# warship_demo_2.net
KiCad netlist of a schematic drawn in Altium Designer
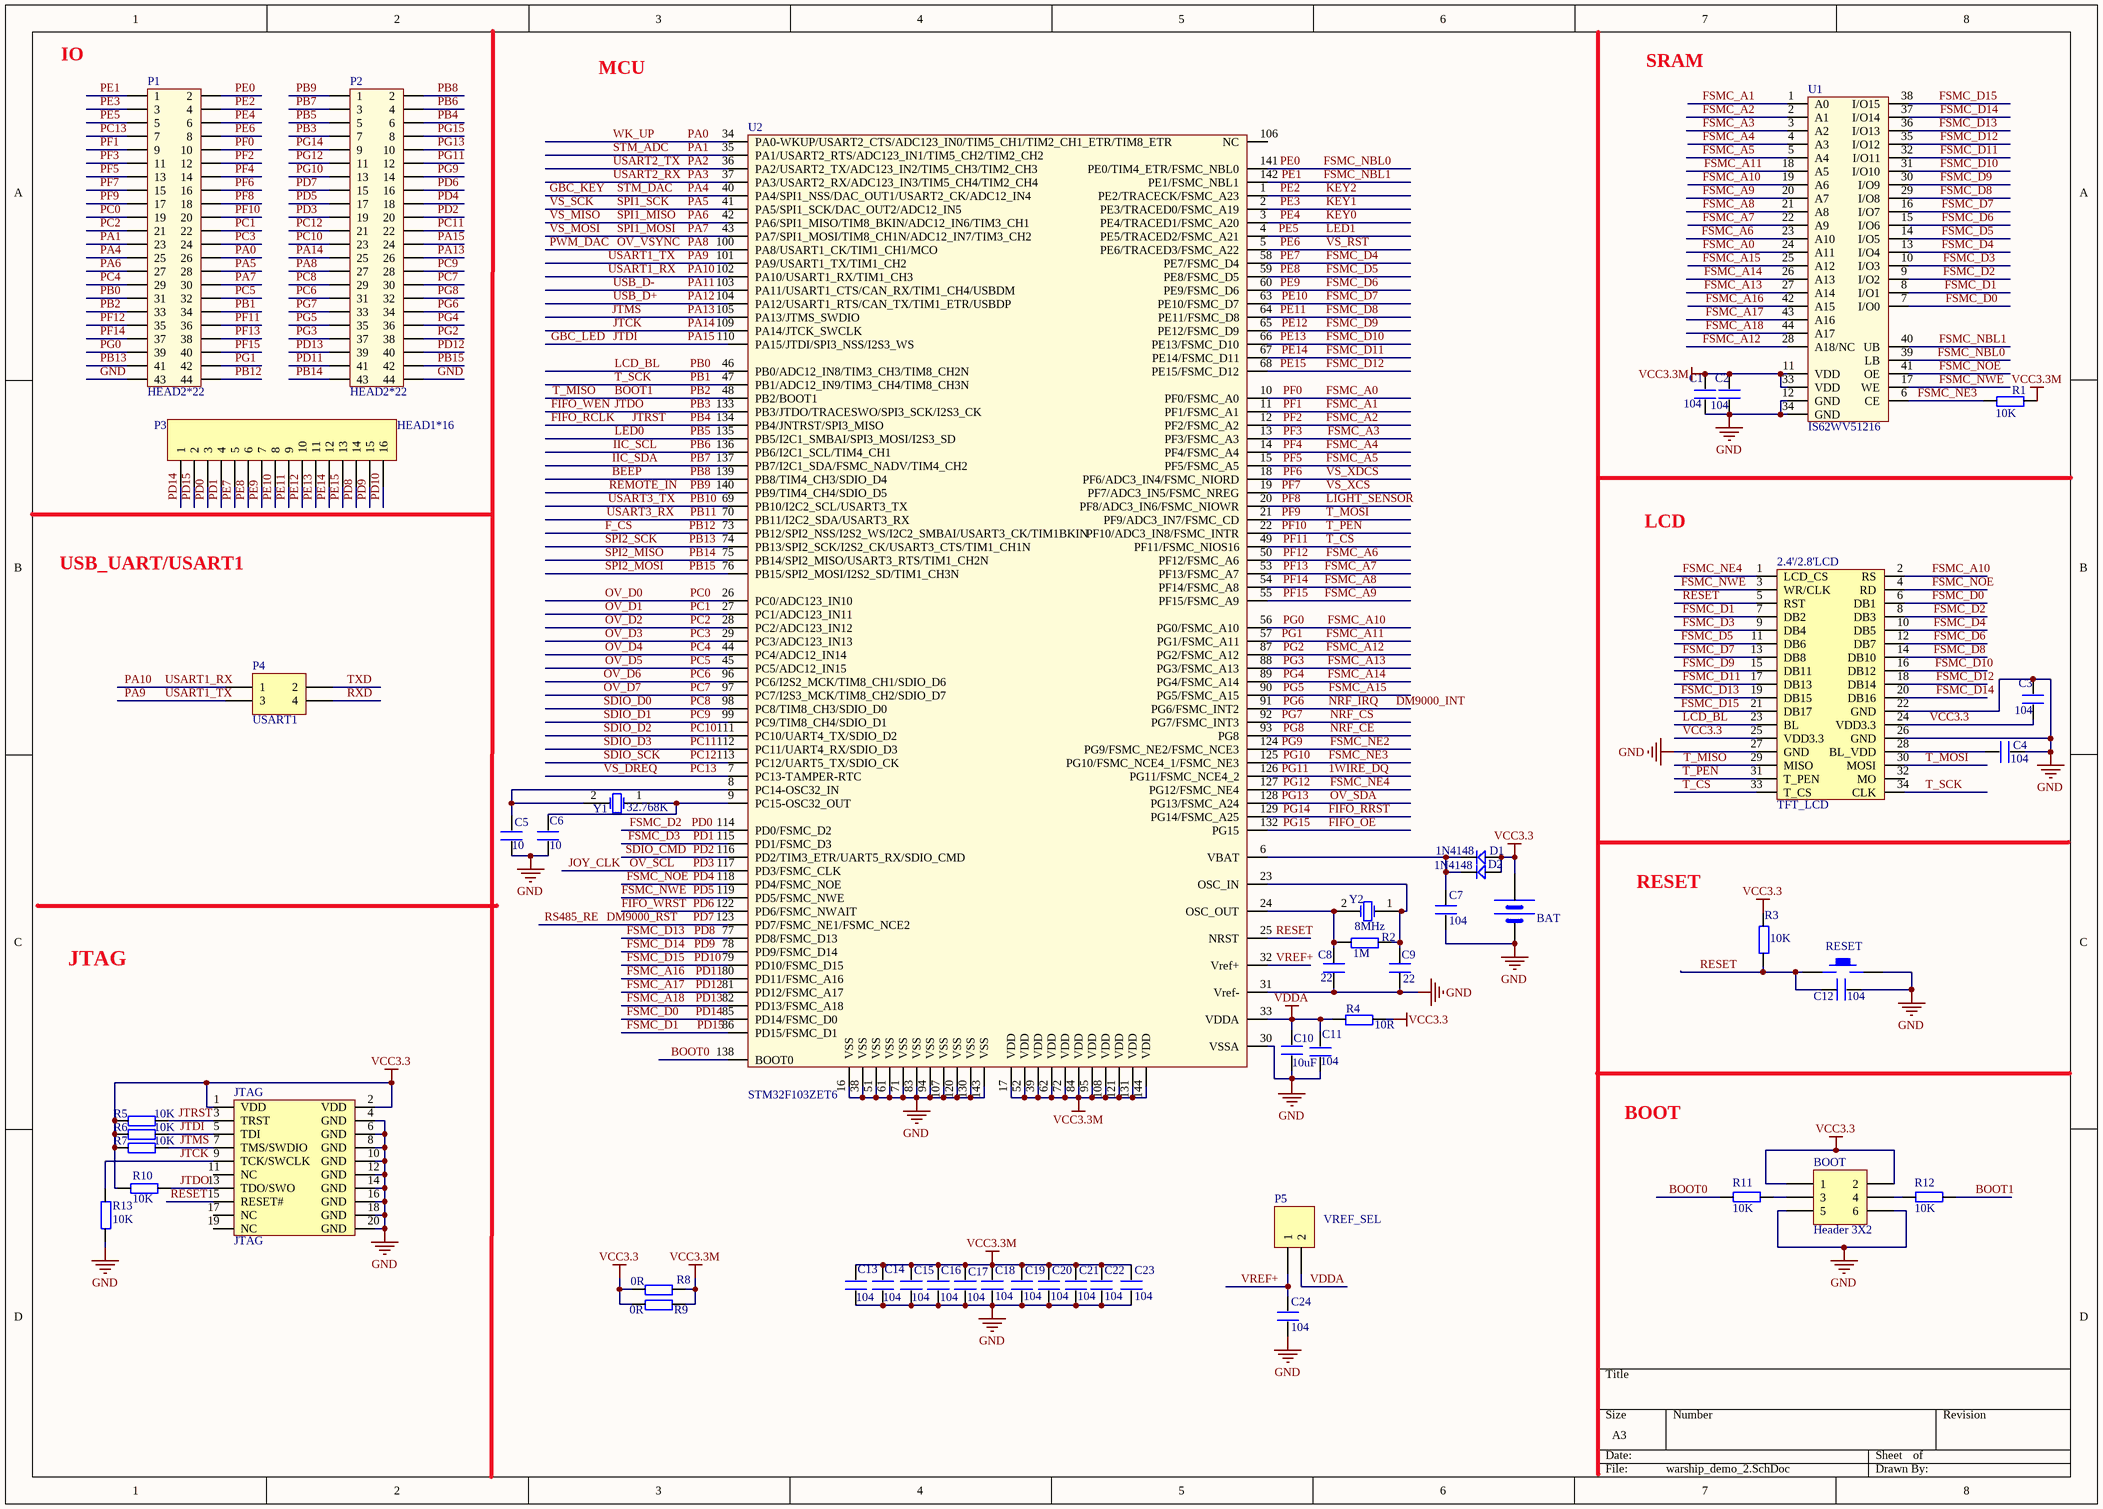
[diagram p0: warship_demo_2.SchDoc]

(export (version "E")
  (design (tool "Eeschema 10.0.6"))
  (components
    (comp (ref "2.4'/2.8'LCD")
      (value "TFT_LCD")
      (footprint "db2*17-4.3")
      (libsource (lib "WarShip V3 STM32103封装库") (part "TFT_LCD"))
    )
    (comp (ref "BAT")
      (value "BATT")
      (footprint "BATM")
      (libsource (lib "WarShip V3 STM32103封装库") (part "BAT"))
    )
    (comp (ref "BOOT")
      (value "Header 3X2")
      (footprint "HDR2X3")
      (description "Header, 3-Pin, Dual row")
      (fields (field (name "PUBLISHER") "Altium Limited"))
      (libsource (lib "WarShip V3 STM32103封装库") (part "Header 3X2"))
    )
    (comp (ref "C1") (value "104") (footprint "0603P") (libsource (lib "WarShip V3 STM32103封装库") (part "C")))
    (comp (ref "C2") (value "104") (footprint "0603P") (libsource (lib "WarShip V3 STM32103封装库") (part "C")))
    (comp (ref "C3") (value "104") (footprint "0603P") (libsource (lib "WarShip V3 STM32103封装库") (part "C")))
    (comp (ref "C4") (value "104") (footprint "0603P") (libsource (lib "WarShip V3 STM32103封装库") (part "C")))
    (comp (ref "C5") (value "10") (footprint "0603P") (libsource (lib "WarShip V3 STM32103封装库") (part "C")))
    (comp (ref "C6") (value "10") (footprint "0603P") (libsource (lib "WarShip V3 STM32103封装库") (part "C")))
    (comp (ref "C7") (value "104") (footprint "0603P") (libsource (lib "WarShip V3 STM32103封装库") (part "C")))
    (comp (ref "C8") (value "22") (footprint "0603P") (libsource (lib "WarShip V3 STM32103封装库") (part "C")))
    (comp (ref "C9") (value "22") (footprint "0603P") (libsource (lib "WarShip V3 STM32103封装库") (part "C")))
    (comp (ref "C10") (value "10uF") (footprint "0805") (libsource (lib "WarShip V3 STM32103封装库") (part "C")))
    (comp (ref "C11") (value "104") (footprint "0603P") (libsource (lib "WarShip V3 STM32103封装库") (part "C")))
    (comp (ref "C12") (value "104") (footprint "0603P") (libsource (lib "WarShip V3 STM32103封装库") (part "C")))
    (comp (ref "C13") (value "104") (footprint "0603P") (libsource (lib "WarShip V3 STM32103封装库") (part "C")))
    (comp (ref "C14") (value "104") (footprint "0603P") (libsource (lib "WarShip V3 STM32103封装库") (part "C")))
    (comp (ref "C15") (value "104") (footprint "0603P") (libsource (lib "WarShip V3 STM32103封装库") (part "C")))
    (comp (ref "C16") (value "104") (footprint "0603P") (libsource (lib "WarShip V3 STM32103封装库") (part "C")))
    (comp (ref "C17") (value "104") (footprint "0603P") (libsource (lib "WarShip V3 STM32103封装库") (part "C")))
    (comp (ref "C18") (value "104") (footprint "0603P") (libsource (lib "WarShip V3 STM32103封装库") (part "C")))
    (comp (ref "C19") (value "104") (footprint "0603P") (libsource (lib "WarShip V3 STM32103封装库") (part "C")))
    (comp (ref "C20") (value "104") (footprint "0603P") (libsource (lib "WarShip V3 STM32103封装库") (part "C")))
    (comp (ref "C21") (value "104") (footprint "0603P") (libsource (lib "WarShip V3 STM32103封装库") (part "C")))
    (comp (ref "C22") (value "104") (footprint "0603P") (libsource (lib "WarShip V3 STM32103封装库") (part "C")))
    (comp (ref "C23") (value "104") (footprint "0603P") (libsource (lib "WarShip V3 STM32103封装库") (part "C")))
    (comp (ref "C24") (value "104") (footprint "0603P") (libsource (lib "WarShip V3 STM32103封装库") (part "C")))
    (comp (ref "D1")
      (value "1N4148")
      (footprint "DIODE_SOP")
      (libsource (lib "WarShip V3 STM32103封装库") (part "D"))
    )
    (comp (ref "D2")
      (value "1N4148")
      (footprint "DIODE_SOP")
      (libsource (lib "WarShip V3 STM32103封装库") (part "D"))
    )
    (comp (ref "JTAG")
      (value "JTAG")
      (footprint "JTAG_20")
      (libsource (lib "WarShip V3 STM32103封装库") (part "JTAG"))
    )
    (comp (ref "P1")
      (value "HEAD2*22")
      (footprint "HEAD2*22")
      (libsource (lib "WarShip V3 STM32103封装库") (part "HEAD2*22"))
    )
    (comp (ref "P2")
      (value "HEAD2*22")
      (footprint "HEAD2*22")
      (libsource (lib "WarShip V3 STM32103封装库") (part "HEAD2*22"))
    )
    (comp (ref "P3")
      (value "HEAD1*16")
      (footprint "HDR1X16")
      (description "Header, 16-Pin")
      (fields (field (name "PUBLISHER") "Altium Limited"))
      (libsource (lib "WarShip V3 STM32103封装库") (part "Header 16"))
    )
    (comp (ref "P4")
      (value "USART1")
      (footprint "HDR2X2")
      (description "Header, 2-Pin, Dual row")
      (fields (field (name "PUBLISHER") "Altium Limited"))
      (libsource (lib "WarShip V3 STM32103封装库") (part "Header 2X2"))
    )
    (comp (ref "P5")
      (value "VREF_SEL")
      (footprint "HDR1X2")
      (description "Header, 2-Pin")
      (fields (field (name "PUBLISHER") "Altium Limited"))
      (libsource (lib "WarShip V3 STM32103封装库") (part "Header 2"))
    )
    (comp (ref "R1") (value "10K") (footprint "0603P") (libsource (lib "WarShip V3 STM32103封装库") (part "R")))
    (comp (ref "R2") (value "1M") (footprint "0603P") (libsource (lib "WarShip V3 STM32103封装库") (part "R")))
    (comp (ref "R3") (value "10K") (footprint "0603P") (libsource (lib "WarShip V3 STM32103封装库") (part "R")))
    (comp (ref "R4") (value "10R") (footprint "0603P") (libsource (lib "WarShip V3 STM32103封装库") (part "R")))
    (comp (ref "R5") (value "10K") (footprint "0603P") (libsource (lib "WarShip V3 STM32103封装库") (part "R")))
    (comp (ref "R6") (value "10K") (footprint "0603P") (libsource (lib "WarShip V3 STM32103封装库") (part "R")))
    (comp (ref "R7") (value "10K") (footprint "0603P") (libsource (lib "WarShip V3 STM32103封装库") (part "R")))
    (comp (ref "R8") (value "0R") (footprint "0603P") (libsource (lib "WarShip V3 STM32103封装库") (part "R")))
    (comp (ref "R9") (value "0R") (footprint "0603P") (libsource (lib "WarShip V3 STM32103封装库") (part "R")))
    (comp (ref "R10") (value "10K") (footprint "0603P") (libsource (lib "WarShip V3 STM32103封装库") (part "R")))
    (comp (ref "R11") (value "10K") (footprint "0603P") (libsource (lib "WarShip V3 STM32103封装库") (part "R")))
    (comp (ref "R12") (value "10K") (footprint "0603P") (libsource (lib "WarShip V3 STM32103封装库") (part "R")))
    (comp (ref "R13") (value "10K") (footprint "0603P") (libsource (lib "WarShip V3 STM32103封装库") (part "R")))
    (comp (ref "RESET")
      (value "KEY_M")
      (footprint "KEY_M")
      (libsource (lib "WarShip V3 STM32103封装库") (part "KEY_M"))
    )
    (comp (ref "U1")
      (value "IS62WV51216")
      (footprint "TSOP44")
      (libsource (lib "WarShip V3 STM32103封装库") (part "IS61LV51216"))
    )
    (comp (ref "U2")
      (value "STM32F103ZET6")
      (footprint "LQFP144")
      (libsource (lib "WarShip V3 STM32103封装库") (part "STM32F103ZET6"))
    )
    (comp (ref "Y1")
      (value "32.768K")
      (footprint "XTAL_US")
      (description "Crystal Oscillator")
      (fields (field (name "PUBLISHER") "Altium Limited"))
      (libsource (lib "WarShip V3 STM32103封装库") (part "XTAL"))
    )
    (comp (ref "Y2")
      (value "8MHz")
      (footprint "XTAL_US")
      (description "Crystal Oscillator")
      (fields (field (name "PUBLISHER") "Altium Limited"))
      (libsource (lib "WarShip V3 STM32103封装库") (part "XTAL"))
    )
  )
  (nets
    (net (code "1") (name "/1WIRE_DQ") (class "Default")
      (node (ref "P2") (pin "12") (pinfunction "12_12") (pintype "passive"))
      (node (ref "U2") (pin "126") (pinfunction "PG11/FSMC_NCE4_2_126") (pintype "passive"))
    )
    (net (code "2") (name "/BEEP") (class "Default")
      (node (ref "P2") (pin "2") (pinfunction "2_2") (pintype "passive"))
      (node (ref "U2") (pin "139") (pinfunction "PB8/TIM4_CH3/SDIO_D4_139") (pintype "passive"))
    )
    (net (code "3") (name "/BOOT0") (class "Default")
      (node (ref "R11") (pin "2") (pintype "passive"))
      (node (ref "U2") (pin "138") (pinfunction "BOOT0_138") (pintype "passive"))
    )
    (net (code "4") (name "/BOOT1") (class "Default")
      (node (ref "2.4'/2.8'LCD") (pin "29") (pinfunction "MISO_29") (pintype "passive"))
      (node (ref "P1") (pin "33") (pinfunction "33_33") (pintype "passive"))
      (node (ref "R12") (pin "1") (pintype "passive"))
      (node (ref "U2") (pin "48") (pinfunction "PB2/BOOT1_48") (pintype "passive"))
    )
    (net (code "5") (name "/DM9000_INT") (class "Default")
      (node (ref "P2") (pin "34") (pinfunction "34_34") (pintype "passive"))
      (node (ref "U2") (pin "91") (pinfunction "PG6/FSMC_INT2_91") (pintype "passive"))
    )
    (net (code "6") (name "/DM9000_RST") (class "Default")
      (node (ref "P2") (pin "15") (pinfunction "15_15") (pintype "passive"))
      (node (ref "U2") (pin "123") (pinfunction "PD7/FSMC_NE1/FSMC_NCE2_123") (pintype "passive"))
    )
    (net (code "7") (name "/FIFO_OE") (class "Default")
      (node (ref "P2") (pin "8") (pinfunction "8_8") (pintype "passive"))
      (node (ref "U2") (pin "132") (pinfunction "PG15_132") (pintype "passive"))
    )
    (net (code "8") (name "/FIFO_RCLK") (class "Default")
      (node (ref "JTAG") (pin "3") (pinfunction "TRST_3") (pintype "passive"))
      (node (ref "P2") (pin "6") (pinfunction "6_6") (pintype "passive"))
      (node (ref "R5") (pin "2") (pintype "passive"))
      (node (ref "U2") (pin "134") (pinfunction "PB4/JNTRST/SPI3_MISO_134") (pintype "passive"))
    )
    (net (code "9") (name "/FIFO_RRST") (class "Default")
      (node (ref "P2") (pin "9") (pinfunction "9_9") (pintype "passive"))
      (node (ref "U2") (pin "129") (pinfunction "PG14/FSMC_A25_129") (pintype "passive"))
    )
    (net (code "10") (name "/FIFO_WEN") (class "Default")
      (node (ref "JTAG") (pin "13") (pinfunction "TDO/SWO_13") (pintype "passive"))
      (node (ref "P2") (pin "7") (pinfunction "7_7") (pintype "passive"))
      (node (ref "R10") (pin "2") (pintype "passive"))
      (node (ref "U2") (pin "133") (pinfunction "PB3/JTDO/TRACESWO/SPI3_SCK/I2S3_CK_133") (pintype "passive"))
    )
    (net (code "11") (name "/FIFO_WRST") (class "Default")
      (node (ref "P2") (pin "16") (pinfunction "16_16") (pintype "passive"))
      (node (ref "U2") (pin "122") (pinfunction "PD6/FSMC_NWAIT_122") (pintype "passive"))
    )
    (net (code "12") (name "/FSMC_A0") (class "Default")
      (node (ref "P1") (pin "10") (pinfunction "10_10") (pintype "passive"))
      (node (ref "U1") (pin "24") (pinfunction "A11_24") (pintype "passive"))
      (node (ref "U2") (pin "10") (pinfunction "PF0/FSMC_A0_10") (pintype "passive"))
    )
    (net (code "13") (name "/FSMC_A1") (class "Default")
      (node (ref "P1") (pin "9") (pinfunction "9_9") (pintype "passive"))
      (node (ref "U1") (pin "1") (pinfunction "A0_1") (pintype "passive"))
      (node (ref "U2") (pin "11") (pinfunction "PF1/FSMC_A1_11") (pintype "passive"))
    )
    (net (code "14") (name "/FSMC_A2") (class "Default")
      (node (ref "P1") (pin "12") (pinfunction "12_12") (pintype "passive"))
      (node (ref "U1") (pin "2") (pinfunction "A1_2") (pintype "passive"))
      (node (ref "U2") (pin "12") (pinfunction "PF2/FSMC_A2_12") (pintype "passive"))
    )
    (net (code "15") (name "/FSMC_A3") (class "Default")
      (node (ref "P1") (pin "11") (pinfunction "11_11") (pintype "passive"))
      (node (ref "U1") (pin "3") (pinfunction "A2_3") (pintype "passive"))
      (node (ref "U2") (pin "13") (pinfunction "PF3/FSMC_A3_13") (pintype "passive"))
    )
    (net (code "16") (name "/FSMC_A4") (class "Default")
      (node (ref "P1") (pin "14") (pinfunction "14_14") (pintype "passive"))
      (node (ref "U1") (pin "4") (pinfunction "A3_4") (pintype "passive"))
      (node (ref "U2") (pin "14") (pinfunction "PF4/FSMC_A4_14") (pintype "passive"))
    )
    (net (code "17") (name "/FSMC_A5") (class "Default")
      (node (ref "P1") (pin "13") (pinfunction "13_13") (pintype "passive"))
      (node (ref "U1") (pin "5") (pinfunction "A4_5") (pintype "passive"))
      (node (ref "U2") (pin "15") (pinfunction "PF5/FSMC_A5_15") (pintype "passive"))
    )
    (net (code "18") (name "/FSMC_A6") (class "Default")
      (node (ref "P1") (pin "35") (pinfunction "35_35") (pintype "passive"))
      (node (ref "U1") (pin "23") (pinfunction "A10_23") (pintype "passive"))
      (node (ref "U2") (pin "50") (pinfunction "PF12/FSMC_A6_50") (pintype "passive"))
    )
    (net (code "19") (name "/FSMC_A7") (class "Default")
      (node (ref "P1") (pin "38") (pinfunction "38_38") (pintype "passive"))
      (node (ref "U1") (pin "22") (pinfunction "A9_22") (pintype "passive"))
      (node (ref "U2") (pin "53") (pinfunction "PF13/FSMC_A7_53") (pintype "passive"))
    )
    (net (code "20") (name "/FSMC_A8") (class "Default")
      (node (ref "P1") (pin "37") (pinfunction "37_37") (pintype "passive"))
      (node (ref "U1") (pin "21") (pinfunction "A8_21") (pintype "passive"))
      (node (ref "U2") (pin "54") (pinfunction "PF14/FSMC_A8_54") (pintype "passive"))
    )
    (net (code "21") (name "/FSMC_A9") (class "Default")
      (node (ref "P1") (pin "40") (pinfunction "40_40") (pintype "passive"))
      (node (ref "U1") (pin "20") (pinfunction "A7_20") (pintype "passive"))
      (node (ref "U2") (pin "55") (pinfunction "PF15/FSMC_A9_55") (pintype "passive"))
    )
    (net (code "22") (name "/FSMC_A10") (class "Default")
      (node (ref "2.4'/2.8'LCD") (pin "2") (pinfunction "RS_2") (pintype "passive"))
      (node (ref "P1") (pin "39") (pinfunction "39_39") (pintype "passive"))
      (node (ref "U1") (pin "19") (pinfunction "A6_19") (pintype "passive"))
      (node (ref "U2") (pin "56") (pinfunction "PG0/FSMC_A10_56") (pintype "passive"))
    )
    (net (code "23") (name "/FSMC_A11") (class "Default")
      (node (ref "P1") (pin "42") (pinfunction "42_42") (pintype "passive"))
      (node (ref "U1") (pin "18") (pinfunction "A5_18") (pintype "passive"))
      (node (ref "U2") (pin "57") (pinfunction "PG1/FSMC_A11_57") (pintype "passive"))
    )
    (net (code "24") (name "/FSMC_A12") (class "Default")
      (node (ref "P2") (pin "38") (pinfunction "38_38") (pintype "passive"))
      (node (ref "U1") (pin "28") (pinfunction "A18/NC_28") (pintype "passive"))
      (node (ref "U2") (pin "87") (pinfunction "PG2/FSMC_A12_87") (pintype "passive"))
    )
    (net (code "25") (name "/FSMC_A13") (class "Default")
      (node (ref "P2") (pin "37") (pinfunction "37_37") (pintype "passive"))
      (node (ref "U1") (pin "27") (pinfunction "A14_27") (pintype "passive"))
      (node (ref "U2") (pin "88") (pinfunction "PG3/FSMC_A13_88") (pintype "passive"))
    )
    (net (code "26") (name "/FSMC_A14") (class "Default")
      (node (ref "P2") (pin "36") (pinfunction "36_36") (pintype "passive"))
      (node (ref "U1") (pin "26") (pinfunction "A13_26") (pintype "passive"))
      (node (ref "U2") (pin "89") (pinfunction "PG4/FSMC_A14_89") (pintype "passive"))
    )
    (net (code "27") (name "/FSMC_A15") (class "Default")
      (node (ref "P2") (pin "35") (pinfunction "35_35") (pintype "passive"))
      (node (ref "U1") (pin "25") (pinfunction "A12_25") (pintype "passive"))
      (node (ref "U2") (pin "90") (pinfunction "PG5/FSMC_A15_90") (pintype "passive"))
    )
    (net (code "28") (name "/FSMC_A16") (class "Default")
      (node (ref "P2") (pin "41") (pinfunction "41_41") (pintype "passive"))
      (node (ref "U1") (pin "42") (pinfunction "A15_42") (pintype "passive"))
      (node (ref "U2") (pin "80") (pinfunction "PD11/FSMC_A16_80") (pintype "passive"))
    )
    (net (code "29") (name "/FSMC_A17") (class "Default")
      (node (ref "P2") (pin "40") (pinfunction "40_40") (pintype "passive"))
      (node (ref "U1") (pin "43") (pinfunction "A16_43") (pintype "passive"))
      (node (ref "U2") (pin "81") (pinfunction "PD12/FSMC_A17_81") (pintype "passive"))
    )
    (net (code "30") (name "/FSMC_A18") (class "Default")
      (node (ref "P2") (pin "39") (pinfunction "39_39") (pintype "passive"))
      (node (ref "U1") (pin "44") (pinfunction "A17_44") (pintype "passive"))
      (node (ref "U2") (pin "82") (pinfunction "PD13/FSMC_A18_82") (pintype "passive"))
    )
    (net (code "31") (name "/FSMC_D0") (class "Default")
      (node (ref "2.4'/2.8'LCD") (pin "6") (pinfunction "DB1_6") (pintype "passive"))
      (node (ref "P3") (pin "1") (pinfunction "1_1") (pintype "passive"))
      (node (ref "U1") (pin "7") (pinfunction "I/O0_7") (pintype "passive"))
      (node (ref "U2") (pin "85") (pinfunction "PD14/FSMC_D0_85") (pintype "passive"))
    )
    (net (code "32") (name "/FSMC_D1") (class "Default")
      (node (ref "2.4'/2.8'LCD") (pin "7") (pinfunction "DB2_7") (pintype "passive"))
      (node (ref "P3") (pin "2") (pinfunction "2_2") (pintype "passive"))
      (node (ref "U1") (pin "8") (pinfunction "I/O1_8") (pintype "passive"))
      (node (ref "U2") (pin "86") (pinfunction "PD15/FSMC_D1_86") (pintype "passive"))
    )
    (net (code "33") (name "/FSMC_D2") (class "Default")
      (node (ref "2.4'/2.8'LCD") (pin "8") (pinfunction "DB3_8") (pintype "passive"))
      (node (ref "P3") (pin "3") (pinfunction "3_3") (pintype "passive"))
      (node (ref "U1") (pin "9") (pinfunction "I/O2_9") (pintype "passive"))
      (node (ref "U2") (pin "114") (pinfunction "PD0/FSMC_D2_114") (pintype "passive"))
    )
    (net (code "34") (name "/FSMC_D3") (class "Default")
      (node (ref "2.4'/2.8'LCD") (pin "9") (pinfunction "DB4_9") (pintype "passive"))
      (node (ref "P3") (pin "4") (pinfunction "4_4") (pintype "passive"))
      (node (ref "U1") (pin "10") (pinfunction "I/O3_10") (pintype "passive"))
      (node (ref "U2") (pin "115") (pinfunction "PD1/FSMC_D3_115") (pintype "passive"))
    )
    (net (code "35") (name "/FSMC_D4") (class "Default")
      (node (ref "2.4'/2.8'LCD") (pin "10") (pinfunction "DB5_10") (pintype "passive"))
      (node (ref "P3") (pin "5") (pinfunction "5_5") (pintype "passive"))
      (node (ref "U1") (pin "13") (pinfunction "I/O4_13") (pintype "passive"))
      (node (ref "U2") (pin "58") (pinfunction "PE7/FSMC_D4_58") (pintype "passive"))
    )
    (net (code "36") (name "/FSMC_D5") (class "Default")
      (node (ref "2.4'/2.8'LCD") (pin "11") (pinfunction "DB6_11") (pintype "passive"))
      (node (ref "P3") (pin "6") (pinfunction "6_6") (pintype "passive"))
      (node (ref "U1") (pin "14") (pinfunction "I/O5_14") (pintype "passive"))
      (node (ref "U2") (pin "59") (pinfunction "PE8/FSMC_D5_59") (pintype "passive"))
    )
    (net (code "37") (name "/FSMC_D6") (class "Default")
      (node (ref "2.4'/2.8'LCD") (pin "12") (pinfunction "DB7_12") (pintype "passive"))
      (node (ref "P3") (pin "7") (pinfunction "7_7") (pintype "passive"))
      (node (ref "U1") (pin "15") (pinfunction "I/O6_15") (pintype "passive"))
      (node (ref "U2") (pin "60") (pinfunction "PE9/FSMC_D6_60") (pintype "passive"))
    )
    (net (code "38") (name "/FSMC_D7") (class "Default")
      (node (ref "2.4'/2.8'LCD") (pin "13") (pinfunction "DB8_13") (pintype "passive"))
      (node (ref "P3") (pin "8") (pinfunction "8_8") (pintype "passive"))
      (node (ref "U1") (pin "16") (pinfunction "I/O7_16") (pintype "passive"))
      (node (ref "U2") (pin "63") (pinfunction "PE10/FSMC_D7_63") (pintype "passive"))
    )
    (net (code "39") (name "/FSMC_D8") (class "Default")
      (node (ref "2.4'/2.8'LCD") (pin "14") (pinfunction "DB10_14") (pintype "passive"))
      (node (ref "P3") (pin "9") (pinfunction "9_9") (pintype "passive"))
      (node (ref "U1") (pin "29") (pinfunction "I/O8_29") (pintype "passive"))
      (node (ref "U2") (pin "64") (pinfunction "PE11/FSMC_D8_64") (pintype "passive"))
    )
    (net (code "40") (name "/FSMC_D9") (class "Default")
      (node (ref "2.4'/2.8'LCD") (pin "15") (pinfunction "DB11_15") (pintype "passive"))
      (node (ref "P3") (pin "10") (pinfunction "10_10") (pintype "passive"))
      (node (ref "U1") (pin "30") (pinfunction "I/O9_30") (pintype "passive"))
      (node (ref "U2") (pin "65") (pinfunction "PE12/FSMC_D9_65") (pintype "passive"))
    )
    (net (code "41") (name "/FSMC_D10") (class "Default")
      (node (ref "2.4'/2.8'LCD") (pin "16") (pinfunction "DB12_16") (pintype "passive"))
      (node (ref "P3") (pin "11") (pinfunction "11_11") (pintype "passive"))
      (node (ref "U1") (pin "31") (pinfunction "I/O10_31") (pintype "passive"))
      (node (ref "U2") (pin "66") (pinfunction "PE13/FSMC_D10_66") (pintype "passive"))
    )
    (net (code "42") (name "/FSMC_D11") (class "Default")
      (node (ref "2.4'/2.8'LCD") (pin "17") (pinfunction "DB13_17") (pintype "passive"))
      (node (ref "P3") (pin "12") (pinfunction "12_12") (pintype "passive"))
      (node (ref "U1") (pin "32") (pinfunction "I/O11_32") (pintype "passive"))
      (node (ref "U2") (pin "67") (pinfunction "PE14/FSMC_D11_67") (pintype "passive"))
    )
    (net (code "43") (name "/FSMC_D12") (class "Default")
      (node (ref "2.4'/2.8'LCD") (pin "18") (pinfunction "DB14_18") (pintype "passive"))
      (node (ref "P3") (pin "13") (pinfunction "13_13") (pintype "passive"))
      (node (ref "U1") (pin "35") (pinfunction "I/O12_35") (pintype "passive"))
      (node (ref "U2") (pin "68") (pinfunction "PE15/FSMC_D12_68") (pintype "passive"))
    )
    (net (code "44") (name "/FSMC_D13") (class "Default")
      (node (ref "2.4'/2.8'LCD") (pin "19") (pinfunction "DB15_19") (pintype "passive"))
      (node (ref "P3") (pin "14") (pinfunction "14_14") (pintype "passive"))
      (node (ref "U1") (pin "36") (pinfunction "I/O13_36") (pintype "passive"))
      (node (ref "U2") (pin "77") (pinfunction "PD8/FSMC_D13_77") (pintype "passive"))
    )
    (net (code "45") (name "/FSMC_D14") (class "Default")
      (node (ref "2.4'/2.8'LCD") (pin "20") (pinfunction "DB16_20") (pintype "passive"))
      (node (ref "P3") (pin "15") (pinfunction "15_15") (pintype "passive"))
      (node (ref "U1") (pin "37") (pinfunction "I/O14_37") (pintype "passive"))
      (node (ref "U2") (pin "78") (pinfunction "PD9/FSMC_D14_78") (pintype "passive"))
    )
    (net (code "46") (name "/FSMC_D15") (class "Default")
      (node (ref "2.4'/2.8'LCD") (pin "21") (pinfunction "DB17_21") (pintype "passive"))
      (node (ref "P3") (pin "16") (pinfunction "16_16") (pintype "passive"))
      (node (ref "U1") (pin "38") (pinfunction "I/O15_38") (pintype "passive"))
      (node (ref "U2") (pin "79") (pinfunction "PD10/FSMC_D15_79") (pintype "passive"))
    )
    (net (code "47") (name "/FSMC_NBL0") (class "Default")
      (node (ref "P1") (pin "2") (pinfunction "2_2") (pintype "passive"))
      (node (ref "U1") (pin "39") (pinfunction "LB_39") (pintype "passive"))
      (node (ref "U2") (pin "141") (pinfunction "PE0/TIM4_ETR/FSMC_NBL0_141") (pintype "passive"))
    )
    (net (code "48") (name "/FSMC_NBL1") (class "Default")
      (node (ref "P1") (pin "1") (pinfunction "1_1") (pintype "passive"))
      (node (ref "U1") (pin "40") (pinfunction "UB_40") (pintype "passive"))
      (node (ref "U2") (pin "142") (pinfunction "PE1/FSMC_NBL1_142") (pintype "passive"))
    )
    (net (code "49") (name "/FSMC_NE2") (class "Default")
      (node (ref "P2") (pin "14") (pinfunction "14_14") (pintype "passive"))
      (node (ref "U2") (pin "124") (pinfunction "PG9/FSMC_NE2/FSMC_NCE3_124") (pintype "passive"))
    )
    (net (code "50") (name "/FSMC_NE3") (class "Default")
      (node (ref "P2") (pin "13") (pinfunction "13_13") (pintype "passive"))
      (node (ref "R1") (pin "1") (pintype "passive"))
      (node (ref "U1") (pin "6") (pinfunction "CE_6") (pintype "passive"))
      (node (ref "U2") (pin "125") (pinfunction "PG10/FSMC_NCE4_1/FSMC_NE3_125") (pintype "passive"))
    )
    (net (code "51") (name "/FSMC_NE4") (class "Default")
      (node (ref "2.4'/2.8'LCD") (pin "1") (pinfunction "LCD_CS_1") (pintype "passive"))
      (node (ref "P2") (pin "11") (pinfunction "11_11") (pintype "passive"))
      (node (ref "U2") (pin "127") (pinfunction "PG12/FSMC_NE4_127") (pintype "passive"))
    )
    (net (code "52") (name "/FSMC_NOE") (class "Default")
      (node (ref "2.4'/2.8'LCD") (pin "4") (pinfunction "RD_4") (pintype "passive"))
      (node (ref "P2") (pin "18") (pinfunction "18_18") (pintype "passive"))
      (node (ref "U1") (pin "41") (pinfunction "OE_41") (pintype "passive"))
      (node (ref "U2") (pin "118") (pinfunction "PD4/FSMC_NOE_118") (pintype "passive"))
    )
    (net (code "53") (name "/FSMC_NWE") (class "Default")
      (node (ref "2.4'/2.8'LCD") (pin "3") (pinfunction "WR/CLK_3") (pintype "passive"))
      (node (ref "P2") (pin "17") (pinfunction "17_17") (pintype "passive"))
      (node (ref "U1") (pin "17") (pinfunction "WE_17") (pintype "passive"))
      (node (ref "U2") (pin "119") (pinfunction "PD5/FSMC_NWE_119") (pintype "passive"))
    )
    (net (code "54") (name "/F_CS") (class "Default")
      (node (ref "P1") (pin "44") (pinfunction "44_44") (pintype "passive"))
      (node (ref "U2") (pin "73") (pinfunction "PB12/SPI2_NSS/I2S2_WS/I2C2_SMBAI/USART3_CK/TIM1BKIN_73") (pintype "passive"))
    )
    (net (code "55") (name "/GBC_KEY") (class "Default")
      (node (ref "P1") (pin "25") (pinfunction "25_25") (pintype "passive"))
      (node (ref "U2") (pin "40") (pinfunction "PA4/SPI1_NSS/DAC_OUT1/USART2_CK/ADC12_IN4_40") (pintype "passive"))
    )
    (net (code "56") (name "/GBC_LED") (class "Default")
      (node (ref "JTAG") (pin "5") (pinfunction "TDI_5") (pintype "passive"))
      (node (ref "P2") (pin "24") (pinfunction "24_24") (pintype "passive"))
      (node (ref "R6") (pin "2") (pintype "passive"))
      (node (ref "U2") (pin "110") (pinfunction "PA15/JTDI/SPI3_NSS/I2S3_WS_110") (pintype "passive"))
    )
    (net (code "57") (name "/IIC_SCL") (class "Default")
      (node (ref "P2") (pin "4") (pinfunction "4_4") (pintype "passive"))
      (node (ref "U2") (pin "136") (pinfunction "PB6/I2C1_SCL/TIM4_CH1_136") (pintype "passive"))
    )
    (net (code "58") (name "/IIC_SDA") (class "Default")
      (node (ref "P2") (pin "3") (pinfunction "3_3") (pintype "passive"))
      (node (ref "U2") (pin "137") (pinfunction "PB7/I2C1_SDA/FSMC_NADV/TIM4_CH2_137") (pintype "passive"))
    )
    (net (code "59") (name "/JOY_CLK") (class "Default")
      (node (ref "P2") (pin "19") (pinfunction "19_19") (pintype "passive"))
      (node (ref "U2") (pin "117") (pinfunction "PD3/FSMC_CLK_117") (pintype "passive"))
    )
    (net (code "60") (name "/JTCK") (class "Default")
      (node (ref "JTAG") (pin "9") (pinfunction "TCK/SWCLK_9") (pintype "passive"))
      (node (ref "P2") (pin "25") (pinfunction "25_25") (pintype "passive"))
      (node (ref "R13") (pin "2") (pintype "passive"))
      (node (ref "U2") (pin "109") (pinfunction "PA14/JTCK_SWCLK_109") (pintype "passive"))
    )
    (net (code "61") (name "/JTMS") (class "Default")
      (node (ref "JTAG") (pin "7") (pinfunction "TMS/SWDIO_7") (pintype "passive"))
      (node (ref "P2") (pin "26") (pinfunction "26_26") (pintype "passive"))
      (node (ref "R7") (pin "2") (pintype "passive"))
      (node (ref "U2") (pin "105") (pinfunction "PA13/JTMS_SWDIO_105") (pintype "passive"))
    )
    (net (code "62") (name "/KEY0") (class "Default")
      (node (ref "P1") (pin "6") (pinfunction "6_6") (pintype "passive"))
      (node (ref "U2") (pin "3") (pinfunction "PE4/TRACED1/FSMC_A20_3") (pintype "passive"))
    )
    (net (code "63") (name "/KEY1") (class "Default")
      (node (ref "P1") (pin "3") (pinfunction "3_3") (pintype "passive"))
      (node (ref "U2") (pin "2") (pinfunction "PE3/TRACED0/FSMC_A19_2") (pintype "passive"))
    )
    (net (code "64") (name "/KEY2") (class "Default")
      (node (ref "P1") (pin "4") (pinfunction "4_4") (pintype "passive"))
      (node (ref "U2") (pin "1") (pinfunction "PE2/TRACECK/FSMC_A23_1") (pintype "passive"))
    )
    (net (code "65") (name "/LCD_BL") (class "Default")
      (node (ref "2.4'/2.8'LCD") (pin "23") (pinfunction "BL_23") (pintype "passive"))
      (node (ref "P1") (pin "31") (pinfunction "31_31") (pintype "passive"))
      (node (ref "U2") (pin "46") (pinfunction "PB0/ADC12_IN8/TIM3_CH3/TIM8_CH2N_46") (pintype "passive"))
    )
    (net (code "66") (name "/LED0") (class "Default")
      (node (ref "P2") (pin "5") (pinfunction "5_5") (pintype "passive"))
      (node (ref "U2") (pin "135") (pinfunction "PB5/I2C1_SMBAI/SPI3_MOSI/I2S3_SD_135") (pintype "passive"))
    )
    (net (code "67") (name "/LED1") (class "Default")
      (node (ref "P1") (pin "5") (pinfunction "5_5") (pintype "passive"))
      (node (ref "U2") (pin "4") (pinfunction "PE5/TRACED2/FSMC_A21_4") (pintype "passive"))
    )
    (net (code "68") (name "/LIGHT_SENSOR") (class "Default")
      (node (ref "P1") (pin "18") (pinfunction "18_18") (pintype "passive"))
      (node (ref "U2") (pin "20") (pinfunction "PF8/ADC3_IN6/FSMC_NIOWR_20") (pintype "passive"))
    )
    (net (code "69") (name "/NRF_CE") (class "Default")
      (node (ref "P2") (pin "32") (pinfunction "32_32") (pintype "passive"))
      (node (ref "U2") (pin "93") (pinfunction "PG8_93") (pintype "passive"))
    )
    (net (code "70") (name "/NRF_CS") (class "Default")
      (node (ref "P2") (pin "33") (pinfunction "33_33") (pintype "passive"))
      (node (ref "U2") (pin "92") (pinfunction "PG7/FSMC_INT3_92") (pintype "passive"))
    )
    (net (code "71") (name "/OV_D0") (class "Default")
      (node (ref "P1") (pin "19") (pinfunction "19_19") (pintype "passive"))
      (node (ref "U2") (pin "26") (pinfunction "PC0/ADC123_IN10_26") (pintype "passive"))
    )
    (net (code "72") (name "/OV_D1") (class "Default")
      (node (ref "P1") (pin "22") (pinfunction "22_22") (pintype "passive"))
      (node (ref "U2") (pin "27") (pinfunction "PC1/ADC123_IN11_27") (pintype "passive"))
    )
    (net (code "73") (name "/OV_D2") (class "Default")
      (node (ref "P1") (pin "21") (pinfunction "21_21") (pintype "passive"))
      (node (ref "U2") (pin "28") (pinfunction "PC2/ADC123_IN12_28") (pintype "passive"))
    )
    (net (code "74") (name "/OV_D3") (class "Default")
      (node (ref "P1") (pin "24") (pinfunction "24_24") (pintype "passive"))
      (node (ref "U2") (pin "29") (pinfunction "PC3/ADC123_IN13_29") (pintype "passive"))
    )
    (net (code "75") (name "/OV_D4") (class "Default")
      (node (ref "P1") (pin "29") (pinfunction "29_29") (pintype "passive"))
      (node (ref "U2") (pin "44") (pinfunction "PC4/ADC12_IN14_44") (pintype "passive"))
    )
    (net (code "76") (name "/OV_D5") (class "Default")
      (node (ref "P1") (pin "32") (pinfunction "32_32") (pintype "passive"))
      (node (ref "U2") (pin "45") (pinfunction "PC5/ADC12_IN15_45") (pintype "passive"))
    )
    (net (code "77") (name "/OV_D6") (class "Default")
      (node (ref "P2") (pin "31") (pinfunction "31_31") (pintype "passive"))
      (node (ref "U2") (pin "96") (pinfunction "PC6/I2S2_MCK/TIM8_CH1/SDIO_D6_96") (pintype "passive"))
    )
    (net (code "78") (name "/OV_D7") (class "Default")
      (node (ref "P2") (pin "30") (pinfunction "30_30") (pintype "passive"))
      (node (ref "U2") (pin "97") (pinfunction "PC7/I2S3_MCK/TIM8_CH2/SDIO_D7_97") (pintype "passive"))
    )
    (net (code "79") (name "/OV_SDA") (class "Default")
      (node (ref "P2") (pin "10") (pinfunction "10_10") (pintype "passive"))
      (node (ref "U2") (pin "128") (pinfunction "PG13/FSMC_A24_128") (pintype "passive"))
    )
    (net (code "80") (name "/OV_VSYNC") (class "Default")
      (node (ref "P2") (pin "27") (pinfunction "27_27") (pintype "passive"))
      (node (ref "U2") (pin "100") (pinfunction "PA8/USART1_CK/TIM1_CH1/MCO_100") (pintype "passive"))
    )
    (net (code "81") (name "/PA0") (class "Default")
      (node (ref "P1") (pin "26") (pinfunction "26_26") (pintype "passive"))
      (node (ref "U2") (pin "34") (pinfunction "PA0-WKUP/USART2_CTS/ADC123_IN0/TIM5_CH1/TIM2_CH1_ETR/TIM8_ETR_34") (pintype "passive"))
    )
    (net (code "82") (name "/PA1") (class "Default")
      (node (ref "P1") (pin "23") (pinfunction "23_23") (pintype "passive"))
      (node (ref "U2") (pin "35") (pinfunction "PA1/USART2_RTS/ADC123_IN1/TIM5_CH2/TIM2_CH2_35") (pintype "passive"))
    )
    (net (code "83") (name "/PA2") (class "Default")
      (node (ref "U2") (pin "36") (pinfunction "PA2/USART2_TX/ADC123_IN2/TIM5_CH3/TIM2_CH3_36") (pintype "passive"))
    )
    (net (code "84") (name "/PA3") (class "Default")
      (node (ref "U2") (pin "37") (pinfunction "PA3/USART2_RX/ADC123_IN3/TIM5_CH4/TIM2_CH4_37") (pintype "passive"))
    )
    (net (code "85") (name "/PA5") (class "Default")
      (node (ref "P1") (pin "28") (pinfunction "28_28") (pintype "passive"))
      (node (ref "U2") (pin "41") (pinfunction "PA5/SPI1_SCK/DAC_OUT2/ADC12_IN5_41") (pintype "passive"))
    )
    (net (code "86") (name "/PA6") (class "Default")
      (node (ref "P1") (pin "27") (pinfunction "27_27") (pintype "passive"))
      (node (ref "U2") (pin "42") (pinfunction "PA6/SPI1_MISO/TIM8_BKIN/ADC12_IN6/TIM3_CH1_42") (pintype "passive"))
    )
    (net (code "87") (name "/PA7") (class "Default")
      (node (ref "P1") (pin "30") (pinfunction "30_30") (pintype "passive"))
      (node (ref "U2") (pin "43") (pinfunction "PA7/SPI1_MOSI/TIM8_CH1N/ADC12_IN7/TIM3_CH2_43") (pintype "passive"))
    )
    (net (code "88") (name "/PA9") (class "Default")
      (node (ref "P4") (pin "3") (pinfunction "3_3") (pintype "passive"))
      (node (ref "U2") (pin "101") (pinfunction "PA9/USART1_TX/TIM1_CH2_101") (pintype "passive"))
    )
    (net (code "89") (name "/PA10") (class "Default")
      (node (ref "P4") (pin "1") (pinfunction "1_1") (pintype "passive"))
      (node (ref "U2") (pin "102") (pinfunction "PA10/USART1_RX/TIM1_CH3_102") (pintype "passive"))
    )
    (net (code "90") (name "/PA11") (class "Default")
      (node (ref "U2") (pin "103") (pinfunction "PA11/USART1_CTS/CAN_RX/TIM1_CH4/USBDM_103") (pintype "passive"))
    )
    (net (code "91") (name "/PA12") (class "Default")
      (node (ref "U2") (pin "104") (pinfunction "PA12/USART1_RTS/CAN_TX/TIM1_ETR/USBDP_104") (pintype "passive"))
    )
    (net (code "92") (name "/PB1") (class "Default")
      (node (ref "2.4'/2.8'LCD") (pin "34") (pinfunction "CLK_34") (pintype "passive"))
      (node (ref "P1") (pin "34") (pinfunction "34_34") (pintype "passive"))
      (node (ref "U2") (pin "47") (pinfunction "PB1/ADC12_IN9/TIM3_CH4/TIM8_CH3N_47") (pintype "passive"))
    )
    (net (code "93") (name "/PB9") (class "Default")
      (node (ref "P2") (pin "1") (pinfunction "1_1") (pintype "passive"))
      (node (ref "U2") (pin "140") (pinfunction "PB9/TIM4_CH4/SDIO_D5_140") (pintype "passive"))
    )
    (net (code "94") (name "/PB10") (class "Default")
      (node (ref "U2") (pin "69") (pinfunction "PB10/I2C2_SCL/USART3_TX_69") (pintype "passive"))
    )
    (net (code "95") (name "/PB11") (class "Default")
      (node (ref "U2") (pin "70") (pinfunction "PB11/I2C2_SDA/USART3_RX_70") (pintype "passive"))
    )
    (net (code "96") (name "/PB13") (class "Default")
      (node (ref "P1") (pin "41") (pinfunction "41_41") (pintype "passive"))
      (node (ref "U2") (pin "74") (pinfunction "PB13/SPI2_SCK/I2S2_CK/USART3_CTS/TIM1_CH1N_74") (pintype "passive"))
    )
    (net (code "97") (name "/PB14") (class "Default")
      (node (ref "P2") (pin "43") (pinfunction "43_43") (pintype "passive"))
      (node (ref "U2") (pin "75") (pinfunction "PB14/SPI2_MISO/USART3_RTS/TIM1_CH2N_75") (pintype "passive"))
    )
    (net (code "98") (name "/PB15") (class "Default")
      (node (ref "P2") (pin "42") (pinfunction "42_42") (pintype "passive"))
      (node (ref "U2") (pin "76") (pinfunction "PB15/SPI2_MOSI/I2S2_SD/TIM1_CH3N_76") (pintype "passive"))
    )
    (net (code "99") (name "/PC8") (class "Default")
      (node (ref "P2") (pin "29") (pinfunction "29_29") (pintype "passive"))
      (node (ref "U2") (pin "98") (pinfunction "PC8/TIM8_CH3/SDIO_D0_98") (pintype "passive"))
    )
    (net (code "100") (name "/PC9") (class "Default")
      (node (ref "P2") (pin "28") (pinfunction "28_28") (pintype "passive"))
      (node (ref "U2") (pin "99") (pinfunction "PC9/TIM8_CH4/SDIO_D1_99") (pintype "passive"))
    )
    (net (code "101") (name "/PC10") (class "Default")
      (node (ref "P2") (pin "23") (pinfunction "23_23") (pintype "passive"))
      (node (ref "U2") (pin "111") (pinfunction "PC10/UART4_TX/SDIO_D2_111") (pintype "passive"))
    )
    (net (code "102") (name "/PC11") (class "Default")
      (node (ref "P2") (pin "22") (pinfunction "22_22") (pintype "passive"))
      (node (ref "U2") (pin "112") (pinfunction "PC11/UART4_RX/SDIO_D3_112") (pintype "passive"))
    )
    (net (code "103") (name "/PC12") (class "Default")
      (node (ref "P2") (pin "21") (pinfunction "21_21") (pintype "passive"))
      (node (ref "U2") (pin "113") (pinfunction "PC12/UART5_TX/SDIO_CK_113") (pintype "passive"))
    )
    (net (code "104") (name "/PC13") (class "Default")
      (node (ref "P1") (pin "7") (pinfunction "7_7") (pintype "passive"))
      (node (ref "U2") (pin "7") (pinfunction "PC13-TAMPER-RTC_7") (pintype "passive"))
    )
    (net (code "105") (name "/PD2") (class "Default")
      (node (ref "P2") (pin "20") (pinfunction "20_20") (pintype "passive"))
      (node (ref "U2") (pin "116") (pinfunction "PD2/TIM3_ETR/UART5_RX/SDIO_CMD_116") (pintype "passive"))
    )
    (net (code "106") (name "/PE6") (class "Default")
      (node (ref "P1") (pin "8") (pinfunction "8_8") (pintype "passive"))
      (node (ref "U2") (pin "5") (pinfunction "PE6/TRACED3/FSMC_A22_5") (pintype "passive"))
    )
    (net (code "107") (name "/PF6") (class "Default")
      (node (ref "P1") (pin "16") (pinfunction "16_16") (pintype "passive"))
      (node (ref "U2") (pin "18") (pinfunction "PF6/ADC3_IN4/FSMC_NIORD_18") (pintype "passive"))
    )
    (net (code "108") (name "/PF7") (class "Default")
      (node (ref "P1") (pin "15") (pinfunction "15_15") (pintype "passive"))
      (node (ref "U2") (pin "19") (pinfunction "PF7/ADC3_IN5/FSMC_NREG_19") (pintype "passive"))
    )
    (net (code "109") (name "/PF9") (class "Default")
      (node (ref "2.4'/2.8'LCD") (pin "30") (pinfunction "MOSI_30") (pintype "passive"))
      (node (ref "P1") (pin "17") (pinfunction "17_17") (pintype "passive"))
      (node (ref "U2") (pin "21") (pinfunction "PF9/ADC3_IN7/FSMC_CD_21") (pintype "passive"))
    )
    (net (code "110") (name "/PF10") (class "Default")
      (node (ref "2.4'/2.8'LCD") (pin "31") (pinfunction "T_PEN_31") (pintype "passive"))
      (node (ref "P1") (pin "20") (pinfunction "20_20") (pintype "passive"))
      (node (ref "U2") (pin "22") (pinfunction "PF10/ADC3_IN8/FSMC_INTR_22") (pintype "passive"))
    )
    (net (code "111") (name "/PF11") (class "Default")
      (node (ref "2.4'/2.8'LCD") (pin "33") (pinfunction "T_CS_33") (pintype "passive"))
      (node (ref "P1") (pin "36") (pinfunction "36_36") (pintype "passive"))
      (node (ref "U2") (pin "49") (pinfunction "PF11/FSMC_NIOS16_49") (pintype "passive"))
    )
    (net (code "112") (name "/RESET") (class "Default")
      (node (ref "2.4'/2.8'LCD") (pin "5") (pinfunction "RST_5") (pintype "passive"))
      (node (ref "C12") (pin "1") (pintype "passive"))
      (node (ref "JTAG") (pin "15") (pinfunction "RESET#_15") (pintype "passive"))
      (node (ref "R3") (pin "1") (pintype "passive"))
      (node (ref "RESET") (pin "1") (pinfunction "1_1") (pintype "passive"))
      (node (ref "U2") (pin "25") (pinfunction "NRST_25") (pintype "passive"))
    )
    (net (code "113") (name "/RXD") (class "Default")
      (node (ref "P4") (pin "4") (pinfunction "4_4") (pintype "passive"))
    )
    (net (code "114") (name "/TXD") (class "Default")
      (node (ref "P4") (pin "2") (pinfunction "2_2") (pintype "passive"))
    )
    (net (code "115") (name "/VREF+") (class "Default")
      (node (ref "C24") (pin "2") (pintype "passive"))
      (node (ref "P5") (pin "1") (pinfunction "1_1") (pintype "passive"))
      (node (ref "U2") (pin "32") (pinfunction "Vref+_32") (pintype "passive"))
    )
    (net (code "116") (name "GND") (class "Default")
      (node (ref "2.4'/2.8'LCD") (pin "22") (pinfunction "GND_22") (pintype "passive"))
      (node (ref "2.4'/2.8'LCD") (pin "26") (pinfunction "GND_26") (pintype "passive"))
      (node (ref "2.4'/2.8'LCD") (pin "27") (pinfunction "GND_27") (pintype "passive"))
      (node (ref "BAT") (pin "2") (pinfunction "GND_2") (pintype "passive"))
      (node (ref "BOOT") (pin "5") (pinfunction "5_5") (pintype "passive"))
      (node (ref "BOOT") (pin "6") (pinfunction "6_6") (pintype "passive"))
      (node (ref "C1") (pin "1") (pintype "passive"))
      (node (ref "C10") (pin "1") (pintype "passive"))
      (node (ref "C11") (pin "2") (pintype "passive"))
      (node (ref "C12") (pin "2") (pintype "passive"))
      (node (ref "C13") (pin "1") (pintype "passive"))
      (node (ref "C14") (pin "1") (pintype "passive"))
      (node (ref "C15") (pin "1") (pintype "passive"))
      (node (ref "C16") (pin "1") (pintype "passive"))
      (node (ref "C17") (pin "1") (pintype "passive"))
      (node (ref "C18") (pin "1") (pintype "passive"))
      (node (ref "C19") (pin "1") (pintype "passive"))
      (node (ref "C2") (pin "2") (pintype "passive"))
      (node (ref "C20") (pin "1") (pintype "passive"))
      (node (ref "C21") (pin "1") (pintype "passive"))
      (node (ref "C22") (pin "1") (pintype "passive"))
      (node (ref "C23") (pin "1") (pintype "passive"))
      (node (ref "C24") (pin "1") (pintype "passive"))
      (node (ref "C3") (pin "1") (pintype "passive"))
      (node (ref "C4") (pin "2") (pintype "passive"))
      (node (ref "C5") (pin "1") (pintype "passive"))
      (node (ref "C6") (pin "1") (pintype "passive"))
      (node (ref "C7") (pin "1") (pintype "passive"))
      (node (ref "C8") (pin "1") (pintype "passive"))
      (node (ref "C9") (pin "2") (pintype "passive"))
      (node (ref "JTAG") (pin "10") (pinfunction "GND_10") (pintype "passive"))
      (node (ref "JTAG") (pin "12") (pinfunction "GND_12") (pintype "passive"))
      (node (ref "JTAG") (pin "14") (pinfunction "GND_14") (pintype "passive"))
      (node (ref "JTAG") (pin "16") (pinfunction "GND_16") (pintype "passive"))
      (node (ref "JTAG") (pin "18") (pinfunction "GND_18") (pintype "passive"))
      (node (ref "JTAG") (pin "20") (pinfunction "GND_20") (pintype "passive"))
      (node (ref "JTAG") (pin "4") (pinfunction "GND_4") (pintype "passive"))
      (node (ref "JTAG") (pin "6") (pinfunction "GND_6") (pintype "passive"))
      (node (ref "JTAG") (pin "8") (pinfunction "GND_8") (pintype "passive"))
      (node (ref "P1") (pin "43") (pinfunction "43_43") (pintype "passive"))
      (node (ref "P2") (pin "44") (pinfunction "44_44") (pintype "passive"))
      (node (ref "R13") (pin "1") (pintype "passive"))
      (node (ref "RESET") (pin "2") (pinfunction "2_2") (pintype "passive"))
      (node (ref "U1") (pin "12") (pinfunction "GND_12") (pintype "passive"))
      (node (ref "U1") (pin "34") (pinfunction "GND_34") (pintype "passive"))
      (node (ref "U2") (pin "107") (pinfunction "VSS_107") (pintype "passive"))
      (node (ref "U2") (pin "120") (pinfunction "VSS_120") (pintype "passive"))
      (node (ref "U2") (pin "130") (pinfunction "VSS_130") (pintype "passive"))
      (node (ref "U2") (pin "143") (pinfunction "VSS_143") (pintype "passive"))
      (node (ref "U2") (pin "16") (pinfunction "VSS_16") (pintype "passive"))
      (node (ref "U2") (pin "30") (pinfunction "VSSA_30") (pintype "passive"))
      (node (ref "U2") (pin "31") (pinfunction "Vref-_31") (pintype "passive"))
      (node (ref "U2") (pin "38") (pinfunction "VSS_38") (pintype "passive"))
      (node (ref "U2") (pin "51") (pinfunction "VSS_51") (pintype "passive"))
      (node (ref "U2") (pin "61") (pinfunction "VSS_61") (pintype "passive"))
      (node (ref "U2") (pin "71") (pinfunction "VSS_71") (pintype "passive"))
      (node (ref "U2") (pin "83") (pinfunction "VSS_83") (pintype "passive"))
      (node (ref "U2") (pin "94") (pinfunction "VSS_94") (pintype "passive"))
    )
    (net (code "117") (name "Net-(2.4'/2.8'LCD-BL_VDD)") (class "Default")
      (node (ref "2.4'/2.8'LCD") (pin "28") (pinfunction "BL_VDD_28") (pintype "passive"))
      (node (ref "C4") (pin "1") (pintype "passive"))
    )
    (net (code "118") (name "Net-(BOOT-Pad3)") (class "Default")
      (node (ref "BOOT") (pin "3") (pinfunction "3_3") (pintype "passive"))
      (node (ref "R11") (pin "1") (pintype "passive"))
    )
    (net (code "119") (name "Net-(BOOT-Pad4)") (class "Default")
      (node (ref "BOOT") (pin "4") (pinfunction "4_4") (pintype "passive"))
      (node (ref "R12") (pin "2") (pintype "passive"))
    )
    (net (code "120") (name "Net-(U2-OSC_IN)") (class "Default")
      (node (ref "C9") (pin "1") (pintype "passive"))
      (node (ref "R2") (pin "2") (pintype "passive"))
      (node (ref "U2") (pin "23") (pinfunction "OSC_IN_23") (pintype "passive"))
      (node (ref "Y2") (pin "1") (pinfunction "OSC1_1") (pintype "passive"))
    )
    (net (code "121") (name "Net-(U2-OSC_OUT)") (class "Default")
      (node (ref "C8") (pin "2") (pintype "passive"))
      (node (ref "R2") (pin "1") (pintype "passive"))
      (node (ref "U2") (pin "24") (pinfunction "OSC_OUT_24") (pintype "passive"))
      (node (ref "Y2") (pin "2") (pinfunction "OSC2_2") (pintype "passive"))
    )
    (net (code "122") (name "Net-(U2-PC14-OSC32_IN)") (class "Default")
      (node (ref "C5") (pin "2") (pintype "passive"))
      (node (ref "U2") (pin "8") (pinfunction "PC14-OSC32_IN_8") (pintype "passive"))
      (node (ref "Y1") (pin "2") (pinfunction "OSC2_2") (pintype "passive"))
    )
    (net (code "123") (name "Net-(U2-PC15-OSC32_OUT)") (class "Default")
      (node (ref "C6") (pin "2") (pintype "passive"))
      (node (ref "U2") (pin "9") (pinfunction "PC15-OSC32_OUT_9") (pintype "passive"))
      (node (ref "Y1") (pin "1") (pinfunction "OSC1_1") (pintype "passive"))
    )
    (net (code "124") (name "Net-(U2-VBAT)") (class "Default")
      (node (ref "C7") (pin "2") (pintype "passive"))
      (node (ref "D1") (pin "2") (pintype "passive"))
      (node (ref "D2") (pin "2") (pintype "passive"))
      (node (ref "U2") (pin "6") (pinfunction "VBAT_6") (pintype "passive"))
    )
    (net (code "125") (name "VCC3.3") (class "Default")
      (node (ref "2.4'/2.8'LCD") (pin "24") (pinfunction "VDD3.3_24") (pintype "passive"))
      (node (ref "2.4'/2.8'LCD") (pin "25") (pinfunction "VDD3.3_25") (pintype "passive"))
      (node (ref "BAT") (pin "1") (pinfunction "VCC_1") (pintype "passive"))
      (node (ref "BOOT") (pin "1") (pinfunction "1_1") (pintype "passive"))
      (node (ref "BOOT") (pin "2") (pinfunction "2_2") (pintype "passive"))
      (node (ref "C3") (pin "2") (pintype "passive"))
      (node (ref "D1") (pin "1") (pintype "passive"))
      (node (ref "D2") (pin "1") (pintype "passive"))
      (node (ref "JTAG") (pin "1") (pinfunction "VDD_1") (pintype "passive"))
      (node (ref "JTAG") (pin "2") (pinfunction "VDD_2") (pintype "passive"))
      (node (ref "R10") (pin "1") (pintype "passive"))
      (node (ref "R3") (pin "2") (pintype "passive"))
      (node (ref "R4") (pin "2") (pintype "passive"))
      (node (ref "R5") (pin "1") (pintype "passive"))
      (node (ref "R6") (pin "1") (pintype "passive"))
      (node (ref "R7") (pin "1") (pintype "passive"))
      (node (ref "R8") (pin "1") (pintype "passive"))
      (node (ref "R9") (pin "1") (pintype "passive"))
    )
    (net (code "126") (name "VCC3.3M") (class "Default")
      (node (ref "C1") (pin "2") (pintype "passive"))
      (node (ref "C13") (pin "2") (pintype "passive"))
      (node (ref "C14") (pin "2") (pintype "passive"))
      (node (ref "C15") (pin "2") (pintype "passive"))
      (node (ref "C16") (pin "2") (pintype "passive"))
      (node (ref "C17") (pin "2") (pintype "passive"))
      (node (ref "C18") (pin "2") (pintype "passive"))
      (node (ref "C19") (pin "2") (pintype "passive"))
      (node (ref "C2") (pin "1") (pintype "passive"))
      (node (ref "C20") (pin "2") (pintype "passive"))
      (node (ref "C21") (pin "2") (pintype "passive"))
      (node (ref "C22") (pin "2") (pintype "passive"))
      (node (ref "C23") (pin "2") (pintype "passive"))
      (node (ref "R1") (pin "2") (pintype "passive"))
      (node (ref "R8") (pin "2") (pintype "passive"))
      (node (ref "R9") (pin "2") (pintype "passive"))
      (node (ref "U1") (pin "11") (pinfunction "VDD_11") (pintype "passive"))
      (node (ref "U1") (pin "33") (pinfunction "VDD_33") (pintype "passive"))
      (node (ref "U2") (pin "108") (pinfunction "VDD_108") (pintype "passive"))
      (node (ref "U2") (pin "121") (pinfunction "VDD_121") (pintype "passive"))
      (node (ref "U2") (pin "131") (pinfunction "VDD_131") (pintype "passive"))
      (node (ref "U2") (pin "144") (pinfunction "VDD_144") (pintype "passive"))
      (node (ref "U2") (pin "17") (pinfunction "VDD_17") (pintype "passive"))
      (node (ref "U2") (pin "39") (pinfunction "VDD_39") (pintype "passive"))
      (node (ref "U2") (pin "52") (pinfunction "VDD_52") (pintype "passive"))
      (node (ref "U2") (pin "62") (pinfunction "VDD_62") (pintype "passive"))
      (node (ref "U2") (pin "72") (pinfunction "VDD_72") (pintype "passive"))
      (node (ref "U2") (pin "84") (pinfunction "VDD_84") (pintype "passive"))
      (node (ref "U2") (pin "95") (pinfunction "VDD_95") (pintype "passive"))
    )
    (net (code "127") (name "VDDA") (class "Default")
      (node (ref "C10") (pin "2") (pintype "passive"))
      (node (ref "C11") (pin "1") (pintype "passive"))
      (node (ref "P5") (pin "2") (pinfunction "2_2") (pintype "passive"))
      (node (ref "R4") (pin "1") (pintype "passive"))
      (node (ref "U2") (pin "33") (pinfunction "VDDA_33") (pintype "passive"))
    )
    (net (code "128") (name "unconnected-(2.4'/2.8'LCD-MO-Pad32)") (class "Default")
      (node (ref "2.4'/2.8'LCD") (pin "32") (pinfunction "MO_32") (pintype "passive"))
    )
    (net (code "129") (name "unconnected-(JTAG-NC-Pad11)") (class "Default")
      (node (ref "JTAG") (pin "11") (pinfunction "NC_11") (pintype "passive"))
    )
    (net (code "130") (name "unconnected-(JTAG-NC-Pad17)") (class "Default")
      (node (ref "JTAG") (pin "17") (pinfunction "NC_17") (pintype "passive"))
    )
    (net (code "131") (name "unconnected-(JTAG-NC-Pad19)") (class "Default")
      (node (ref "JTAG") (pin "19") (pinfunction "NC_19") (pintype "passive"))
    )
    (net (code "132") (name "unconnected-(U2-NC-Pad106)") (class "Default")
      (node (ref "U2") (pin "106") (pinfunction "NC_106") (pintype "passive"))
    )
  )
)
